# bh_rs485_0_alph.net
KiCad netlist of a schematic drawn in Altium Designer
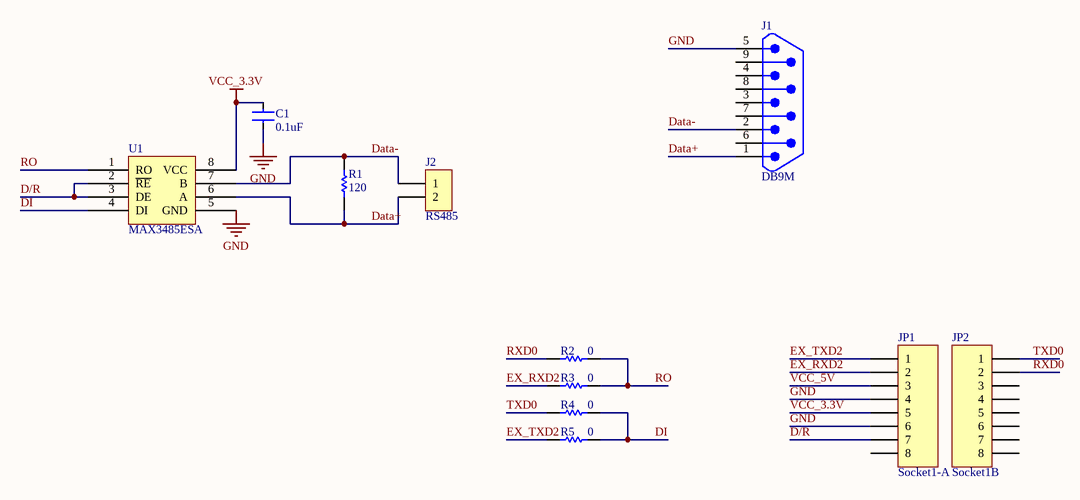
[diagram p0: bh_rs485_0_alph.SchDoc]

(export (version "E")
  (design (tool "Eeschema 10.0.6"))
  (components
    (comp (ref "C1")
      (value "0.1uF")
      (footprint "C0603")
      (description "SMD-CAP")
      (libsource (lib "BH_DESIGN_DEVICE") (part "CAP-SMD"))
    )
    (comp (ref "J1")
      (value "DB9M")
      (footprint "DB9/M")
      (description "jointbar")
      (libsource (lib "BH_DESIGN_CONNECTOR") (part "DB9M"))
    )
    (comp (ref "J2")
      (value "RS485")
      (footprint "CON2*0.381")
      (description "Connector")
      (libsource (lib "5D_CONNECTOR") (part "SIP1X2"))
    )
    (comp (ref "JP1")
      (value "Socket1-A")
      (footprint "SIP1x8x2.0")
      (libsource (lib "5D_CONNECTOR") (part "SIP1X8"))
    )
    (comp (ref "JP2")
      (value "Socket1B")
      (footprint "SIP1x8x2.0")
      (description "8 Pin Header")
      (libsource (lib "") (part "SIP1X8_1"))
    )
    (comp (ref "R1")
      (value "120")
      (footprint "R0603")
      (description "Resistor")
      (libsource (lib "BH_DESIGN_DEVICE") (part "RES"))
    )
    (comp (ref "R2")
      (value "0")
      (footprint "R0603")
      (description "Resistor")
      (libsource (lib "BH_DESIGN_DEVICE") (part "RES"))
    )
    (comp (ref "R3")
      (value "0")
      (footprint "R0603")
      (description "Resistor")
      (libsource (lib "BH_DESIGN_DEVICE") (part "RES"))
    )
    (comp (ref "R4")
      (value "0")
      (footprint "R0603")
      (description "Resistor")
      (libsource (lib "BH_DESIGN_DEVICE") (part "RES"))
    )
    (comp (ref "R5")
      (value "0")
      (footprint "R0603")
      (description "Resistor")
      (libsource (lib "BH_DESIGN_DEVICE") (part "RES"))
    )
    (comp (ref "U1")
      (value "MAX3485ESA")
      (footprint "SO-8")
      (description "X9511WP-10K")
      (libsource (lib "5D_IC") (part "MAX3485ESA"))
    )
  )
  (nets
    (net (code "1") (name "/DI") (class "Default")
      (node (ref "R4") (pin "1") (pinfunction "1_1") (pintype "passive"))
      (node (ref "R5") (pin "1") (pinfunction "1_1") (pintype "passive"))
      (node (ref "U1") (pin "4") (pinfunction "DI_4") (pintype "passive"))
    )
    (net (code "2") (name "/Data+") (class "Default")
      (node (ref "J1") (pin "1") (pinfunction "5_1") (pintype "passive"))
      (node (ref "J2") (pin "2") (pinfunction "2_2") (pintype "passive"))
      (node (ref "R1") (pin "1") (pinfunction "1_1") (pintype "passive"))
      (node (ref "U1") (pin "6") (pinfunction "A_6") (pintype "passive"))
    )
    (net (code "3") (name "/Data-") (class "Default")
      (node (ref "J1") (pin "2") (pinfunction "4_2") (pintype "passive"))
      (node (ref "J2") (pin "1") (pinfunction "1_1") (pintype "passive"))
      (node (ref "R1") (pin "2") (pinfunction "2_2") (pintype "passive"))
      (node (ref "U1") (pin "7") (pinfunction "B_7") (pintype "passive"))
    )
    (net (code "4") (name "/D{slash}R") (class "Default")
      (node (ref "JP1") (pin "7") (pinfunction "7_7") (pintype "passive"))
      (node (ref "U1") (pin "2") (pinfunction "~{RE}_2") (pintype "passive"))
      (node (ref "U1") (pin "3") (pinfunction "DE_3") (pintype "passive"))
    )
    (net (code "5") (name "/EX_RXD2") (class "Default")
      (node (ref "JP1") (pin "2") (pinfunction "2_2") (pintype "passive"))
      (node (ref "R3") (pin "2") (pinfunction "2_2") (pintype "passive"))
    )
    (net (code "6") (name "/EX_TXD2") (class "Default")
      (node (ref "JP1") (pin "1") (pinfunction "1_1") (pintype "passive"))
      (node (ref "R5") (pin "2") (pinfunction "2_2") (pintype "passive"))
    )
    (net (code "7") (name "/RO") (class "Default")
      (node (ref "R2") (pin "1") (pinfunction "1_1") (pintype "passive"))
      (node (ref "R3") (pin "1") (pinfunction "1_1") (pintype "passive"))
      (node (ref "U1") (pin "1") (pinfunction "RO_1") (pintype "passive"))
    )
    (net (code "8") (name "/RXD0") (class "Default")
      (node (ref "JP2") (pin "2") (pinfunction "2_2") (pintype "passive"))
      (node (ref "R2") (pin "2") (pinfunction "2_2") (pintype "passive"))
    )
    (net (code "9") (name "/TXD0") (class "Default")
      (node (ref "JP2") (pin "1") (pinfunction "1_1") (pintype "passive"))
      (node (ref "R4") (pin "2") (pinfunction "2_2") (pintype "passive"))
    )
    (net (code "10") (name "/VCC_5V") (class "Default")
      (node (ref "JP1") (pin "3") (pinfunction "3_3") (pintype "passive"))
    )
    (net (code "11") (name "GND") (class "Default")
      (node (ref "C1") (pin "2") (pinfunction "2_2") (pintype "passive"))
      (node (ref "J1") (pin "5") (pinfunction "1_5") (pintype "passive"))
      (node (ref "JP1") (pin "4") (pinfunction "4_4") (pintype "passive"))
      (node (ref "JP1") (pin "6") (pinfunction "6_6") (pintype "passive"))
      (node (ref "U1") (pin "5") (pinfunction "GND_5") (pintype "passive"))
    )
    (net (code "12") (name "VCC_3.3V") (class "Default")
      (node (ref "C1") (pin "1") (pinfunction "1_1") (pintype "passive"))
      (node (ref "JP1") (pin "5") (pinfunction "5_5") (pintype "passive"))
      (node (ref "U1") (pin "8") (pinfunction "VCC_8") (pintype "passive"))
    )
    (net (code "13") (name "unconnected-(J1-2-Pad4)") (class "Default")
      (node (ref "J1") (pin "4") (pinfunction "2_4") (pintype "passive"))
    )
    (net (code "14") (name "unconnected-(J1-6-Pad9)") (class "Default")
      (node (ref "J1") (pin "9") (pinfunction "6_9") (pintype "passive"))
    )
    (net (code "15") (name "unconnected-(J1-7-Pad8)") (class "Default")
      (node (ref "J1") (pin "8") (pinfunction "7_8") (pintype "passive"))
    )
    (net (code "16") (name "unconnected-(J1-8-Pad7)") (class "Default")
      (node (ref "J1") (pin "7") (pinfunction "8_7") (pintype "passive"))
    )
    (net (code "17") (name "unconnected-(J1-9-Pad6)") (class "Default")
      (node (ref "J1") (pin "6") (pinfunction "9_6") (pintype "passive"))
    )
    (net (code "18") (name "unconnected-(J1-Pad3)") (class "Default")
      (node (ref "J1") (pin "3") (pinfunction "3_3") (pintype "passive"))
    )
    (net (code "19") (name "unconnected-(JP1-Pad8)") (class "Default")
      (node (ref "JP1") (pin "8") (pinfunction "8_8") (pintype "passive"))
    )
    (net (code "20") (name "unconnected-(JP2-Pad3)") (class "Default")
      (node (ref "JP2") (pin "3") (pinfunction "3_3") (pintype "passive"))
    )
    (net (code "21") (name "unconnected-(JP2-Pad4)") (class "Default")
      (node (ref "JP2") (pin "4") (pinfunction "4_4") (pintype "passive"))
    )
    (net (code "22") (name "unconnected-(JP2-Pad5)") (class "Default")
      (node (ref "JP2") (pin "5") (pinfunction "5_5") (pintype "passive"))
    )
    (net (code "23") (name "unconnected-(JP2-Pad6)") (class "Default")
      (node (ref "JP2") (pin "6") (pinfunction "6_6") (pintype "passive"))
    )
    (net (code "24") (name "unconnected-(JP2-Pad7)") (class "Default")
      (node (ref "JP2") (pin "7") (pinfunction "7_7") (pintype "passive"))
    )
    (net (code "25") (name "unconnected-(JP2-Pad8)") (class "Default")
      (node (ref "JP2") (pin "8") (pinfunction "8_8") (pintype "passive"))
    )
  )
)
